# easyeda-no-connect.net
KiCad netlist of a schematic drawn in EasyEDA
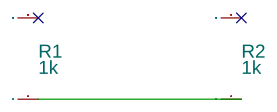
[diagram p0: schematic sheet]

(export (version "E")
  (design (tool "Eeschema 10.0.6"))
  (components
    (comp (ref "R1") (value "1k") (libsource (lib "") (part "Unknown_100_-100")))
    (comp (ref "R2") (value "1k") (libsource (lib "") (part "Unknown_200_-100")))
  )
  (nets
    (net (code "1") (name "Net-(R1-Pad1)") (class "Default")
      (node (ref "R1") (pin "1") (pinfunction "1_1") (pintype "unspecified"))
      (node (ref "R2") (pin "1") (pinfunction "1_1") (pintype "unspecified"))
    )
    (net (code "2") (name "unconnected-(R1-Pad2)") (class "Default")
      (node (ref "R1") (pin "2") (pinfunction "2_2") (pintype "unspecified+no_connect"))
    )
    (net (code "3") (name "unconnected-(R2-Pad2)") (class "Default")
      (node (ref "R2") (pin "2") (pinfunction "2_2") (pintype "unspecified+no_connect"))
    )
  )
)
